# PH_V1_0.net
KiCad netlist of a schematic drawn in Altium Designer
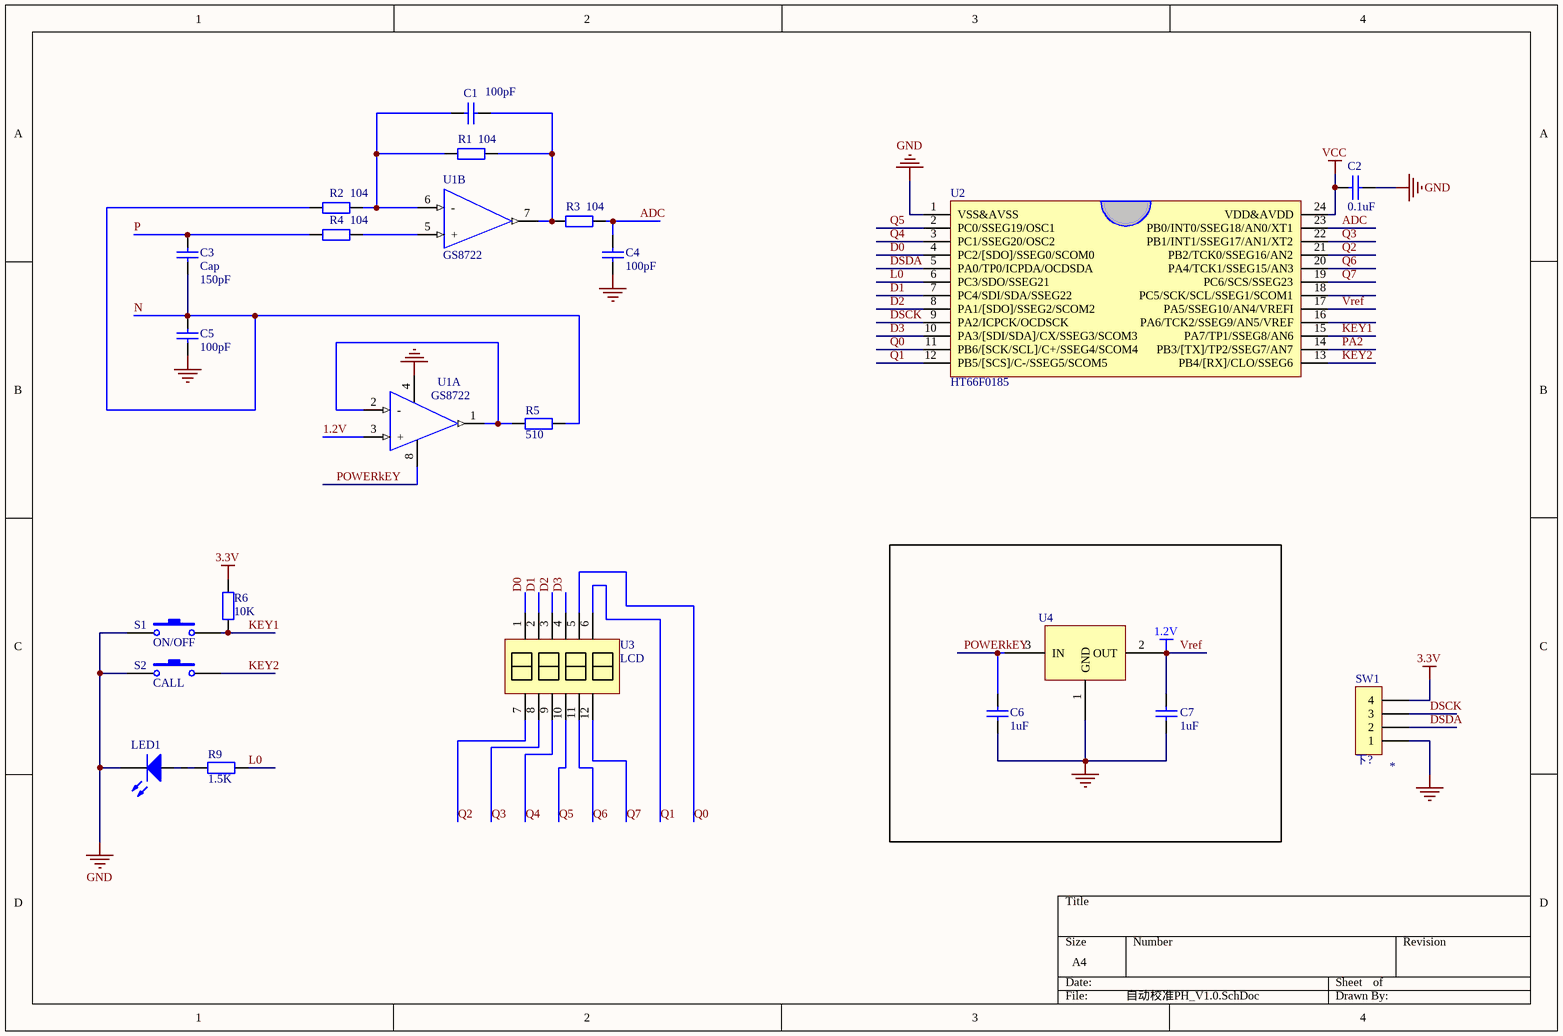
[diagram p0: 自动校准PH_V1.0.SchDoc]

(export (version "E")
  (design (tool "Eeschema 10.0.6"))
  (components
    (comp (ref "C1")
      (value "100pF")
      (footprint "0603")
      (description "Capacitor")
      (fields (field (name "Comment") "Cap") (field (name "PUBLISHER") "Altium Limited"))
      (libsource (lib "Miscellaneous Devices") (part "Cap"))
    )
    (comp (ref "C2")
      (value "0.1uF")
      (footprint "0603")
      (description "Capacitor")
      (libsource (lib "*") (part "CAP"))
    )
    (comp (ref "C3")
      (value "Cap")
      (footprint "0603")
      (description "Capacitor")
      (fields (field (name "ALTIUM_VALUE") "150pF") (field (name "PUBLISHER") "Altium Limited"))
      (libsource (lib "Miscellaneous Devices") (part "Cap"))
    )
    (comp (ref "C4")
      (value "100pF")
      (footprint "0603")
      (description "Capacitor")
      (fields (field (name "Comment") "Cap") (field (name "PUBLISHER") "Altium Limited"))
      (libsource (lib "Miscellaneous Devices") (part "Cap"))
    )
    (comp (ref "C5")
      (value "100pF")
      (footprint "0603")
      (description "Capacitor")
      (fields (field (name "Comment") "Cap") (field (name "PUBLISHER") "Altium Limited"))
      (libsource (lib "Miscellaneous Devices") (part "Cap"))
    )
    (comp (ref "C6")
      (value "1uF")
      (footprint "0603")
      (description "Capacitor")
      (fields
        (field (name "MANUFACTURER") "Generic Components")
        (field (name "PUBLISHER") "Altium Hobart Technology Centre")
      )
      (libsource (lib "*") (part "Cap"))
    )
    (comp (ref "C7")
      (value "1uF")
      (footprint "0603")
      (description "Capacitor")
      (fields
        (field (name "MANUFACTURER") "Generic Components")
        (field (name "PUBLISHER") "Altium Hobart Technology Centre")
      )
      (libsource (lib "*") (part "Cap"))
    )
    (comp (ref "LED1")
      (value "LED1")
      (footprint "LED-1")
      (description "Typical RED GaAs LED")
      (fields (field (name "PUBLISHER") "Altium Limited"))
      (libsource (lib "Miscellaneous Devices") (part "LED1"))
    )
    (comp (ref "R1")
      (value "104")
      (footprint "0603")
      (description "Resistor")
      (fields (field (name "Comment") "Res2") (field (name "PUBLISHER") "Altium Limited"))
      (libsource (lib "Miscellaneous Devices") (part "Res2"))
    )
    (comp (ref "R2")
      (value "104")
      (footprint "0603")
      (description "Resistor")
      (fields (field (name "Comment") "Res2") (field (name "PUBLISHER") "Altium Limited"))
      (libsource (lib "Miscellaneous Devices") (part "Res2"))
    )
    (comp (ref "R3")
      (value "104")
      (footprint "0603")
      (description "Resistor")
      (fields (field (name "Comment") "Res2") (field (name "PUBLISHER") "Altium Limited"))
      (libsource (lib "Miscellaneous Devices") (part "Res2"))
    )
    (comp (ref "R4")
      (value "104")
      (footprint "0603")
      (description "Resistor")
      (fields (field (name "Comment") "Res2") (field (name "PUBLISHER") "Altium Limited"))
      (libsource (lib "Miscellaneous Devices") (part "Res2"))
    )
    (comp (ref "R5")
      (value "510")
      (footprint "0603")
      (description "Resistor")
      (fields (field (name "Comment") "Res2") (field (name "PUBLISHER") "Altium Limited"))
      (libsource (lib "Miscellaneous Devices") (part "Res2"))
    )
    (comp (ref "R6")
      (value "10K")
      (footprint "0603")
      (description "Resistor")
      (fields (field (name "Comment") "Res2") (field (name "PUBLISHER") "Altium Limited"))
      (libsource (lib "") (part "Res2_1"))
    )
    (comp (ref "R9")
      (value "1.5K")
      (footprint "0603")
      (description "Resistor")
      (fields (field (name "Comment") "Res2") (field (name "PUBLISHER") "Altium Limited"))
      (libsource (lib "Miscellaneous Devices") (part "Res2"))
    )
    (comp (ref "S1")
      (value "ON/OFF")
      (footprint "SPST-2")
      (description "Switch")
      (fields (field (name "PUBLISHER") "Altium Limited"))
      (libsource (lib "Miscellaneous Devices") (part "SW-PB"))
    )
    (comp (ref "S2")
      (value "CALL")
      (footprint "SPST-2")
      (description "Switch")
      (fields (field (name "PUBLISHER") "Altium Limited"))
      (libsource (lib "Miscellaneous Devices") (part "SW-PB"))
    )
    (comp (ref "SW1")
      (value "*")
      (footprint "HDR1X4")
      (description "jointbar")
      (fields (field (name "ALTIUM_UNNAMED_1") "下?"))
      (libsource (lib "接口与插座") (part "SIP4"))
    )
    (comp (ref "U1")
      (value "GS8722")
      (footprint "SOIC8")
      (description "LM358-SOP8")
      (libsource (lib "Miscellaneous Devices") (part "LM358"))
    )
    (comp (ref "U2") (value "HT66F0185") (libsource (lib "自动校准PH_V1.0") (part "HT66F0185")))
    (comp (ref "U3") (value "LCD") (footprint "段码") (libsource (lib "Miscellaneous Devices") (part "断码屏-4")))
    (comp (ref "U4") (value "~") (footprint "SOT-23 - LDO") (libsource (lib "*") (part "LM1117")))
  )
  (nets
    (net (code "1") (name "/ADC") (class "Default")
      (node (ref "C4") (pin "2") (pinfunction "2_2") (pintype "passive"))
      (node (ref "R3") (pin "2") (pinfunction "2_2") (pintype "passive"))
      (node (ref "U2") (pin "23") (pinfunction "PB0/INT0/SSEG18/AN0/XT1_23") (pintype "passive"))
    )
    (net (code "2") (name "/D0") (class "Default")
      (node (ref "U2") (pin "4") (pinfunction "PC2/[SDO]/SSEG0/SCOM0_4") (pintype "passive"))
      (node (ref "U3") (pin "1") (pinfunction "13_1") (pintype "passive"))
    )
    (net (code "3") (name "/D1") (class "Default")
      (node (ref "U2") (pin "7") (pinfunction "PC4/SDI/SDA/SSEG22_7") (pintype "passive"))
      (node (ref "U3") (pin "2") (pinfunction "14_2") (pintype "passive"))
    )
    (net (code "4") (name "/D2") (class "Default")
      (node (ref "U2") (pin "8") (pinfunction "PA1/[SDO]/SSEG2/SCOM2_8") (pintype "passive"))
      (node (ref "U3") (pin "3") (pinfunction "15_3") (pintype "passive"))
    )
    (net (code "5") (name "/D3") (class "Default")
      (node (ref "U2") (pin "10") (pinfunction "PA3/[SDI/SDA]/CX/SSEG3/SCOM3_10") (pintype "passive"))
      (node (ref "U3") (pin "4") (pinfunction "16_4") (pintype "passive"))
    )
    (net (code "6") (name "/DSCK") (class "Default")
      (node (ref "SW1") (pin "3") (pinfunction "3_3") (pintype "passive"))
      (node (ref "U2") (pin "9") (pinfunction "PA2/ICPCK/OCDSCK_9") (pintype "passive"))
    )
    (net (code "7") (name "/DSDA") (class "Default")
      (node (ref "SW1") (pin "2") (pinfunction "2_2") (pintype "passive"))
      (node (ref "U2") (pin "5") (pinfunction "PA0/TP0/ICPDA/OCDSDA_5") (pintype "passive"))
    )
    (net (code "8") (name "/KEY1") (class "Default")
      (node (ref "R6") (pin "1") (pinfunction "1_1") (pintype "passive"))
      (node (ref "S1") (pin "2") (pinfunction "2_2") (pintype "passive"))
      (node (ref "U2") (pin "15") (pinfunction "PA7/TP1/SSEG8/AN6_15") (pintype "passive"))
    )
    (net (code "9") (name "/KEY2") (class "Default")
      (node (ref "S2") (pin "2") (pinfunction "2_2") (pintype "passive"))
      (node (ref "U2") (pin "13") (pinfunction "PB4/[RX]/CLO/SSEG6_13") (pintype "passive"))
    )
    (net (code "10") (name "/L0") (class "Default")
      (node (ref "R9") (pin "2") (pinfunction "2_2") (pintype "passive"))
      (node (ref "U2") (pin "6") (pinfunction "PC3/SDO/SSEG21_6") (pintype "passive"))
    )
    (net (code "11") (name "/N") (class "Default")
      (node (ref "C3") (pin "1") (pinfunction "1_1") (pintype "passive"))
      (node (ref "C5") (pin "2") (pinfunction "2_2") (pintype "passive"))
      (node (ref "R2") (pin "1") (pinfunction "1_1") (pintype "passive"))
      (node (ref "R5") (pin "2") (pinfunction "2_2") (pintype "passive"))
    )
    (net (code "12") (name "/P") (class "Default")
      (node (ref "C3") (pin "2") (pinfunction "2_2") (pintype "passive"))
      (node (ref "R4") (pin "1") (pinfunction "1_1") (pintype "passive"))
    )
    (net (code "13") (name "/PA2") (class "Default")
      (node (ref "U2") (pin "14") (pinfunction "PB3/[TX]/TP2/SSEG7/AN7_14") (pintype "passive"))
    )
    (net (code "14") (name "/POWERkEY") (class "Default")
      (node (ref "C6") (pin "2") (pinfunction "2_2") (pintype "passive"))
      (node (ref "U1") (pin "8") (pinfunction "VCC_8") (pintype "power_in"))
      (node (ref "U4") (pin "3") (pinfunction "IN_3") (pintype "passive"))
    )
    (net (code "15") (name "/Q0") (class "Default")
      (node (ref "U2") (pin "11") (pinfunction "PB6/[SCK/SCL]/C+/SSEG4/SCOM4_11") (pintype "passive"))
      (node (ref "U3") (pin "5") (pinfunction "17_5") (pintype "passive"))
    )
    (net (code "16") (name "/Q1") (class "Default")
      (node (ref "U2") (pin "12") (pinfunction "PB5/[SCS]/C-/SSEG5/SCOM5_12") (pintype "passive"))
      (node (ref "U3") (pin "6") (pinfunction "18_6") (pintype "passive"))
    )
    (net (code "17") (name "/Q2") (class "Default")
      (node (ref "U2") (pin "21") (pinfunction "PB2/TCK0/SSEG16/AN2_21") (pintype "passive"))
      (node (ref "U3") (pin "7") (pinfunction "7_7") (pintype "passive"))
    )
    (net (code "18") (name "/Q3") (class "Default")
      (node (ref "U2") (pin "22") (pinfunction "PB1/INT1/SSEG17/AN1/XT2_22") (pintype "passive"))
      (node (ref "U3") (pin "8") (pinfunction "8_8") (pintype "passive"))
    )
    (net (code "19") (name "/Q4") (class "Default")
      (node (ref "U2") (pin "3") (pinfunction "PC1/SSEG20/OSC2_3") (pintype "passive"))
      (node (ref "U3") (pin "9") (pinfunction "9_9") (pintype "passive"))
    )
    (net (code "20") (name "/Q5") (class "Default")
      (node (ref "U2") (pin "2") (pinfunction "PC0/SSEG19/OSC1_2") (pintype "passive"))
      (node (ref "U3") (pin "10") (pinfunction "10_10") (pintype "passive"))
    )
    (net (code "21") (name "/Q6") (class "Default")
      (node (ref "U2") (pin "20") (pinfunction "PA4/TCK1/SSEG15/AN3_20") (pintype "passive"))
      (node (ref "U3") (pin "11") (pinfunction "11_11") (pintype "passive"))
    )
    (net (code "22") (name "/Q7") (class "Default")
      (node (ref "U2") (pin "19") (pinfunction "PC6/SCS/SSEG23_19") (pintype "passive"))
      (node (ref "U3") (pin "12") (pinfunction "9_12") (pintype "passive"))
    )
    (net (code "23") (name "1.2V") (class "Default")
      (node (ref "C7") (pin "2") (pinfunction "2_2") (pintype "passive"))
      (node (ref "U1") (pin "3") (pinfunction "+_3") (pintype "input"))
      (node (ref "U2") (pin "17") (pinfunction "PA5/SSEG10/AN4/VREFI_17") (pintype "passive"))
      (node (ref "U4") (pin "2") (pinfunction "OUT_2") (pintype "passive"))
    )
    (net (code "24") (name "3.3V") (class "Default")
      (node (ref "R6") (pin "2") (pinfunction "2_2") (pintype "passive"))
      (node (ref "SW1") (pin "4") (pinfunction "4_4") (pintype "passive"))
    )
    (net (code "25") (name "GND") (class "Default")
      (node (ref "C2") (pin "2") (pinfunction "2_2") (pintype "passive"))
      (node (ref "C4") (pin "1") (pinfunction "1_1") (pintype "passive"))
      (node (ref "C5") (pin "1") (pinfunction "1_1") (pintype "passive"))
      (node (ref "C6") (pin "1") (pinfunction "1_1") (pintype "passive"))
      (node (ref "C7") (pin "1") (pinfunction "1_1") (pintype "passive"))
      (node (ref "LED1") (pin "2") (pinfunction "K_2") (pintype "passive"))
      (node (ref "S1") (pin "1") (pinfunction "1_1") (pintype "passive"))
      (node (ref "S2") (pin "1") (pinfunction "1_1") (pintype "passive"))
      (node (ref "SW1") (pin "1") (pinfunction "1_1") (pintype "passive"))
      (node (ref "U1") (pin "4") (pinfunction "GND_4") (pintype "power_in"))
      (node (ref "U2") (pin "1") (pinfunction "VSS&AVSS_1") (pintype "passive"))
      (node (ref "U4") (pin "1") (pinfunction "GND_1") (pintype "passive"))
    )
    (net (code "26") (name "Net-(LED1-A)") (class "Default")
      (node (ref "LED1") (pin "1") (pinfunction "A_1") (pintype "passive"))
      (node (ref "R9") (pin "1") (pinfunction "1_1") (pintype "passive"))
    )
    (net (code "27") (name "Net-(U1A--)") (class "Default")
      (node (ref "R5") (pin "1") (pinfunction "1_1") (pintype "passive"))
      (node (ref "U1") (pin "1") (pinfunction "1OUT_1") (pintype "output"))
      (node (ref "U1") (pin "2") (pinfunction "-_2") (pintype "input"))
    )
    (net (code "28") (name "Net-(U1B-+)") (class "Default")
      (node (ref "R4") (pin "2") (pinfunction "2_2") (pintype "passive"))
      (node (ref "U1") (pin "5") (pinfunction "+_5") (pintype "input"))
    )
    (net (code "29") (name "Net-(U1B--)") (class "Default")
      (node (ref "C1") (pin "2") (pinfunction "2_2") (pintype "passive"))
      (node (ref "R1") (pin "1") (pinfunction "1_1") (pintype "passive"))
      (node (ref "R2") (pin "2") (pinfunction "2_2") (pintype "passive"))
      (node (ref "U1") (pin "6") (pinfunction "-_6") (pintype "input"))
    )
    (net (code "30") (name "Net-(U1B-1OUT)") (class "Default")
      (node (ref "C1") (pin "1") (pinfunction "1_1") (pintype "passive"))
      (node (ref "R1") (pin "2") (pinfunction "2_2") (pintype "passive"))
      (node (ref "R3") (pin "1") (pinfunction "1_1") (pintype "passive"))
      (node (ref "U1") (pin "7") (pinfunction "1OUT_7") (pintype "output"))
    )
    (net (code "31") (name "VCC") (class "Default")
      (node (ref "C2") (pin "1") (pinfunction "1_1") (pintype "passive"))
      (node (ref "U2") (pin "24") (pinfunction "VDD&AVDD_24") (pintype "passive"))
    )
    (net (code "32") (name "unconnected-(U2-PA6{slash}TCK2{slash}SSEG9{slash}AN5{slash}VREF-Pad16)") (class "Default")
      (node (ref "U2") (pin "16") (pinfunction "PA6/TCK2/SSEG9/AN5/VREF_16") (pintype "passive"))
    )
    (net (code "33") (name "unconnected-(U2-PC5{slash}SCK{slash}SCL{slash}SSEG1{slash}SCOM1-Pad18)") (class "Default")
      (node (ref "U2") (pin "18") (pinfunction "PC5/SCK/SCL/SSEG1/SCOM1_18") (pintype "passive"))
    )
  )
)
